# power_supply.net
KiCad netlist of a schematic drawn in Altium Designer
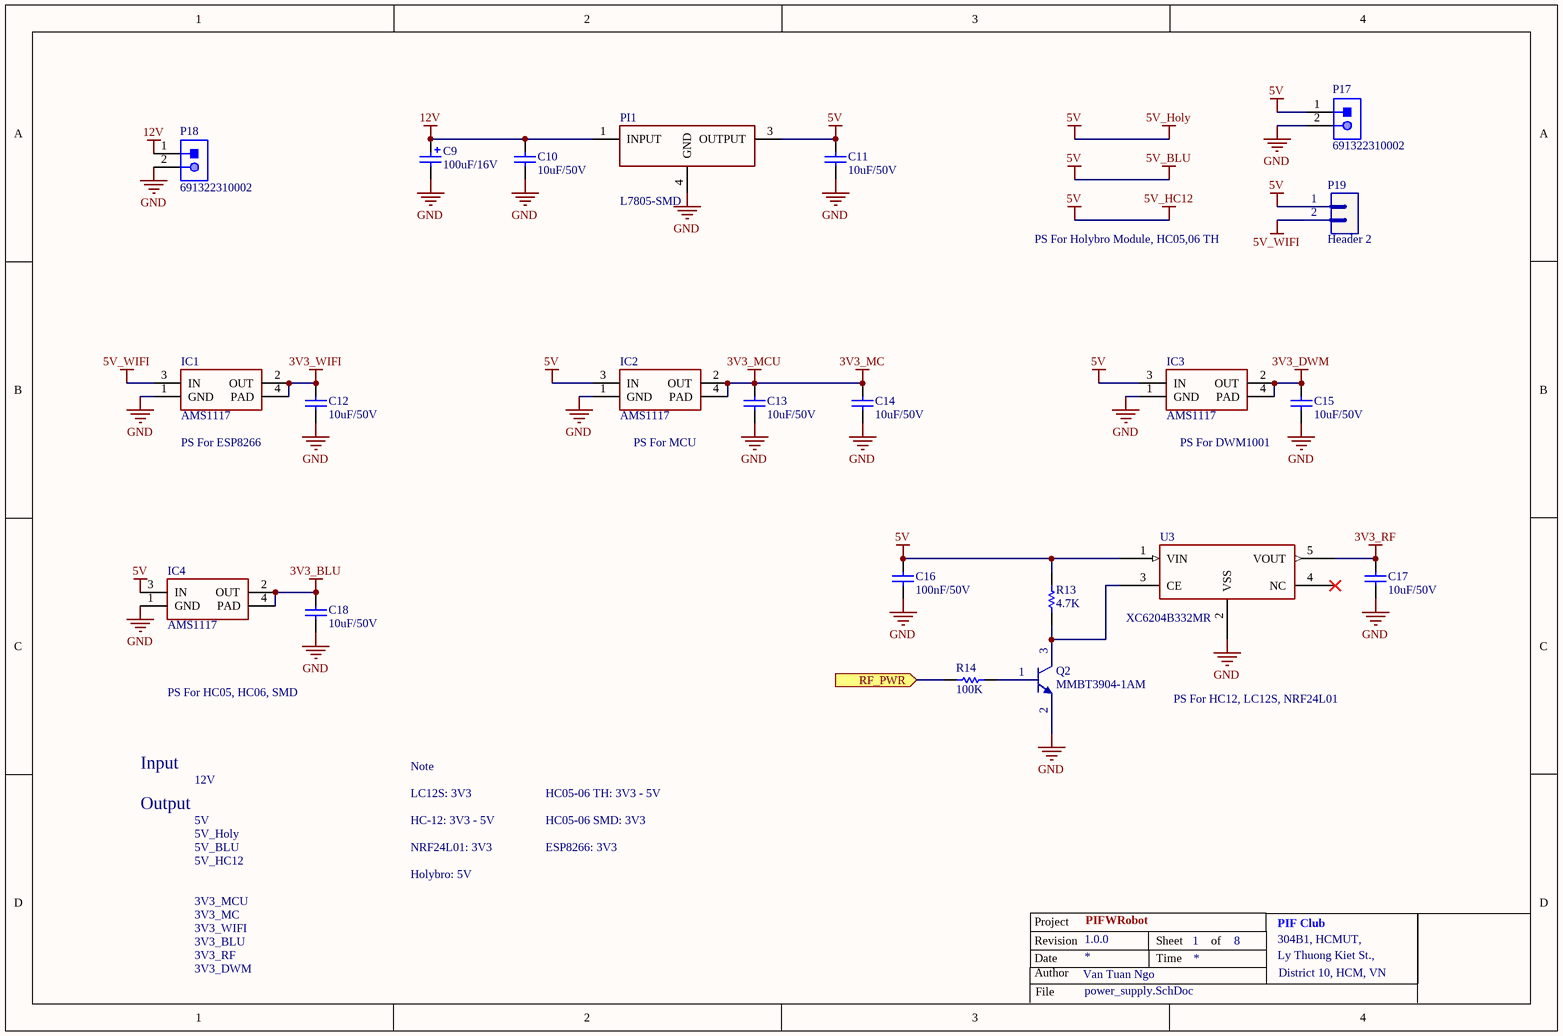
[diagram p0: power_supply.SchDoc]

(export (version "E")
  (design (tool "Eeschema 10.0.6"))
  (components
    (comp (ref "C9")
      (value "100uF/16V")
      (footprint "CAP-SM-AL-SIZE-D-D6L6")
      (description "CAP ALUM 100UF 20% 16V SMD")
      (fields
        (field (name "MANUFACTURER") "Nichicon")
        (field (name "MANUFACTURER PART NUMBER") "UWX1C101MCL1GB")
      )
      (libsource (lib "Capacitor") (part "Cap-Al-100uF-16V-D6L5"))
    )
    (comp (ref "C10")
      (value "10uF/50V")
      (footprint "CAP-SM-0805")
      (description "CAP CER 10UF 50V X5R 0805")
      (fields
        (field (name "MANUFACTURER") "Yageo")
        (field (name "MANUFACTURER PART NUMBER") "CC0805KKX5R9BB106")
      )
      (libsource (lib "Capacitor") (part "Cap-10uF-50V-0805"))
    )
    (comp (ref "C11")
      (value "10uF/50V")
      (footprint "CAP-SM-0805")
      (description "CAP CER 10UF 50V X5R 0805")
      (fields
        (field (name "MANUFACTURER") "Yageo")
        (field (name "MANUFACTURER PART NUMBER") "CC0805KKX5R9BB106")
      )
      (libsource (lib "Capacitor") (part "Cap-10uF-50V-0805"))
    )
    (comp (ref "C12")
      (value "10uF/50V")
      (footprint "CAP-SM-0805")
      (description "CAP CER 10UF 50V X5R 0805")
      (fields
        (field (name "MANUFACTURER") "Yageo")
        (field (name "MANUFACTURER PART NUMBER") "CC0805KKX5R9BB106")
      )
      (libsource (lib "Capacitor") (part "Cap-10uF-50V-0805"))
    )
    (comp (ref "C13")
      (value "10uF/50V")
      (footprint "CAP-SM-0805")
      (description "CAP CER 10UF 50V X5R 0805")
      (fields
        (field (name "MANUFACTURER") "Yageo")
        (field (name "MANUFACTURER PART NUMBER") "CC0805KKX5R9BB106")
      )
      (libsource (lib "Capacitor") (part "Cap-10uF-50V-0805"))
    )
    (comp (ref "C14")
      (value "10uF/50V")
      (footprint "CAP-SM-0805")
      (description "CAP CER 10UF 50V X5R 0805")
      (fields
        (field (name "MANUFACTURER") "Yageo")
        (field (name "MANUFACTURER PART NUMBER") "CC0805KKX5R9BB106")
      )
      (libsource (lib "Capacitor") (part "Cap-10uF-50V-0805"))
    )
    (comp (ref "C15")
      (value "10uF/50V")
      (footprint "CAP-SM-0805")
      (description "CAP CER 10UF 50V X5R 0805")
      (fields
        (field (name "MANUFACTURER") "Yageo")
        (field (name "MANUFACTURER PART NUMBER") "CC0805KKX5R9BB106")
      )
      (libsource (lib "Capacitor") (part "Cap-10uF-50V-0805"))
    )
    (comp (ref "C16")
      (value "100nF/50V")
      (footprint "CAP-SM-0805")
      (description "CAP CER 0.1UF 50V Y5V 0805")
      (fields
        (field (name "MANUFACTURER") "Samsung Electro-Mechanics")
        (field (name "MANUFACTURER PART NUMBER") "CL21F104ZBCNNNC")
      )
      (libsource (lib "Capacitor") (part "Cap-100nF-50V-0805"))
    )
    (comp (ref "C17")
      (value "10uF/50V")
      (footprint "CAP-SM-0805")
      (description "CAP CER 10UF 50V X5R 0805")
      (fields
        (field (name "MANUFACTURER") "Yageo")
        (field (name "MANUFACTURER PART NUMBER") "CC0805KKX5R9BB106")
      )
      (libsource (lib "Capacitor") (part "Cap-10uF-50V-0805"))
    )
    (comp (ref "C18")
      (value "10uF/50V")
      (footprint "CAP-SM-0805")
      (description "CAP CER 10UF 50V X5R 0805")
      (fields
        (field (name "MANUFACTURER") "Yageo")
        (field (name "MANUFACTURER PART NUMBER") "CC0805KKX5R9BB106")
      )
      (libsource (lib "Capacitor") (part "Cap-10uF-50V-0805"))
    )
    (comp (ref "IC1")
      (value "AMS1117")
      (footprint "SOT223")
      (description "Available in 1.8V, 2.5V, 2.85V, 3.3V, 5V, and  Adjustable Versions")
      (libsource (lib "PI") (part "AMS1117"))
    )
    (comp (ref "IC2")
      (value "AMS1117")
      (footprint "SOT223")
      (description "Available in 1.8V, 2.5V, 2.85V, 3.3V, 5V, and  Adjustable Versions")
      (libsource (lib "PI") (part "AMS1117"))
    )
    (comp (ref "IC3")
      (value "AMS1117")
      (footprint "SOT223")
      (description "Available in 1.8V, 2.5V, 2.85V, 3.3V, 5V, and  Adjustable Versions")
      (libsource (lib "PI") (part "AMS1117"))
    )
    (comp (ref "IC4")
      (value "AMS1117")
      (footprint "SOT223")
      (description "Available in 1.8V, 2.5V, 2.85V, 3.3V, 5V, and  Adjustable Versions")
      (libsource (lib "PI") (part "AMS1117"))
    )
    (comp (ref "P17")
      (value "691322310002")
      (footprint "691322310002")
      (description "WR-TBL Serie 322 Horizontal PCB Header, Pluggable, pitch 3.81mm, 2p")
      (fields (field (name "LOCAL SUPPLEIR PART NUMBER") "x") (field (name "PUBLISHER") "Wurth Elektronik"))
      (libsource (lib "terminal_block") (part "691322310002"))
    )
    (comp (ref "P18")
      (value "691322310002")
      (footprint "691322310002")
      (description "WR-TBL Serie 322 Horizontal PCB Header, Pluggable, pitch 3.81mm, 2p")
      (fields (field (name "LOCAL SUPPLEIR PART NUMBER") "x") (field (name "PUBLISHER") "Wurth Elektronik"))
      (libsource (lib "terminal_block") (part "691322310002"))
    )
    (comp (ref "P19")
      (value "Header 2")
      (footprint "JP2")
      (description "Header, 2-Pin")
      (fields (field (name "PUBLISHER") "Altium Limited"))
      (libsource (lib "Header-Connector") (part "Header 2"))
    )
    (comp (ref "PI1")
      (value "L7805-SMD")
      (footprint "TO254P1435X464-4N")
      (libsource (lib "PIFWRobot") (part "L7805-SMD"))
    )
    (comp (ref "Q2")
      (value "MMBT3904-1AM")
      (footprint "SOT23_NEX")
      (libsource (lib "BJT") (part "MMBT3904-1AM"))
    )
    (comp (ref "R13")
      (value "4.7K")
      (footprint "Resistor:RES-SM-0805")
      (description "RES SMD 4.7K OHM 5% 1/8W 0805")
      (fields
        (field (name "MANUFACTURER") "Yageo")
        (field (name "MANUFACTURER PART NUMBER") "RC0805JR-074K7L")
      )
      (libsource (lib "Resistor") (part "Res-4.7K-0805"))
    )
    (comp (ref "R14")
      (value "100K")
      (footprint "Resistor:RES-SM-0805")
      (description "RES 0 OHM JUMPER 0805")
      (fields
        (field (name "MANUFACTURER") "Vishay Dale")
        (field (name "MANUFACTURER PART NUMBER") "WSL080500000ZEA9")
      )
      (libsource (lib "Resistor") (part "Res-100K-0805"))
    )
    (comp (ref "U3")
      (value "XC6204B332MR")
      (footprint "XC6204/05_SOT-00")
      (fields (field (name "COPYRIGHT") "Copyright (C) 2018 Accelerated Designs. All rights reserved"))
      (libsource (lib "PI") (part "XC6204B332MR"))
    )
  )
  (nets
    (net (code "1") (name "/RF_PWR") (class "Default")
      (node (ref "R14") (pin "1") (pinfunction "1_1") (pintype "passive"))
    )
    (net (code "2") (name "3V3_BLU") (class "Default")
      (node (ref "C18") (pin "2") (pinfunction "2_2") (pintype "passive"))
      (node (ref "IC4") (pin "2") (pinfunction "OUT_2") (pintype "passive"))
      (node (ref "IC4") (pin "4") (pinfunction "PAD_4") (pintype "passive"))
    )
    (net (code "3") (name "3V3_DWM") (class "Default")
      (node (ref "C15") (pin "2") (pinfunction "2_2") (pintype "passive"))
      (node (ref "IC3") (pin "2") (pinfunction "OUT_2") (pintype "passive"))
      (node (ref "IC3") (pin "4") (pinfunction "PAD_4") (pintype "passive"))
    )
    (net (code "4") (name "3V3_MC") (class "Default")
      (node (ref "C13") (pin "2") (pinfunction "2_2") (pintype "passive"))
      (node (ref "C14") (pin "2") (pinfunction "2_2") (pintype "passive"))
      (node (ref "IC2") (pin "2") (pinfunction "OUT_2") (pintype "passive"))
      (node (ref "IC2") (pin "4") (pinfunction "PAD_4") (pintype "passive"))
    )
    (net (code "5") (name "3V3_RF") (class "Default")
      (node (ref "C17") (pin "2") (pinfunction "2_2") (pintype "passive"))
      (node (ref "U3") (pin "5") (pinfunction "VOUT_5") (pintype "output"))
    )
    (net (code "6") (name "3V3_WIFI") (class "Default")
      (node (ref "C12") (pin "2") (pinfunction "2_2") (pintype "passive"))
      (node (ref "IC1") (pin "2") (pinfunction "OUT_2") (pintype "passive"))
      (node (ref "IC1") (pin "4") (pinfunction "PAD_4") (pintype "passive"))
    )
    (net (code "7") (name "5V") (class "Default")
      (node (ref "C11") (pin "2") (pinfunction "2_2") (pintype "passive"))
      (node (ref "C16") (pin "2") (pinfunction "2_2") (pintype "passive"))
      (node (ref "IC2") (pin "3") (pinfunction "IN_3") (pintype "passive"))
      (node (ref "IC3") (pin "3") (pinfunction "IN_3") (pintype "passive"))
      (node (ref "IC4") (pin "3") (pinfunction "IN_3") (pintype "passive"))
      (node (ref "P17") (pin "1") (pinfunction "1_1") (pintype "passive"))
      (node (ref "P19") (pin "1") (pinfunction "1_1") (pintype "passive"))
      (node (ref "PI1") (pin "3") (pinfunction "OUTPUT_3") (pintype "passive"))
      (node (ref "R13") (pin "2") (pinfunction "2_2") (pintype "passive"))
      (node (ref "U3") (pin "1") (pinfunction "VIN_1") (pintype "input"))
    )
    (net (code "8") (name "5V_WIFI") (class "Default")
      (node (ref "IC1") (pin "3") (pinfunction "IN_3") (pintype "passive"))
      (node (ref "P19") (pin "2") (pinfunction "2_2") (pintype "passive"))
    )
    (net (code "9") (name "12V") (class "Default")
      (node (ref "C10") (pin "2") (pinfunction "2_2") (pintype "passive"))
      (node (ref "C9") (pin "1") (pinfunction "1_1") (pintype "passive"))
      (node (ref "P18") (pin "1") (pinfunction "1_1") (pintype "passive"))
      (node (ref "PI1") (pin "1") (pinfunction "INPUT_1") (pintype "passive"))
    )
    (net (code "10") (name "GND") (class "Default")
      (node (ref "C10") (pin "1") (pinfunction "1_1") (pintype "passive"))
      (node (ref "C11") (pin "1") (pinfunction "1_1") (pintype "passive"))
      (node (ref "C12") (pin "1") (pinfunction "1_1") (pintype "passive"))
      (node (ref "C13") (pin "1") (pinfunction "1_1") (pintype "passive"))
      (node (ref "C14") (pin "1") (pinfunction "1_1") (pintype "passive"))
      (node (ref "C15") (pin "1") (pinfunction "1_1") (pintype "passive"))
      (node (ref "C16") (pin "1") (pinfunction "1_1") (pintype "passive"))
      (node (ref "C17") (pin "1") (pinfunction "1_1") (pintype "passive"))
      (node (ref "C18") (pin "1") (pinfunction "1_1") (pintype "passive"))
      (node (ref "C9") (pin "2") (pinfunction "2_2") (pintype "passive"))
      (node (ref "IC1") (pin "1") (pinfunction "GND_1") (pintype "passive"))
      (node (ref "IC2") (pin "1") (pinfunction "GND_1") (pintype "passive"))
      (node (ref "IC3") (pin "1") (pinfunction "GND_1") (pintype "passive"))
      (node (ref "IC4") (pin "1") (pinfunction "GND_1") (pintype "passive"))
      (node (ref "P17") (pin "2") (pinfunction "2_2") (pintype "passive"))
      (node (ref "P18") (pin "2") (pinfunction "2_2") (pintype "passive"))
      (node (ref "PI1") (pin "4") (pinfunction "GND_4") (pintype "passive"))
      (node (ref "Q2") (pin "2") (pinfunction "E_2") (pintype "passive"))
      (node (ref "U3") (pin "2") (pinfunction "VSS_2") (pintype "passive"))
    )
    (net (code "11") (name "Net-(Q2-B)") (class "Default")
      (node (ref "Q2") (pin "1") (pinfunction "B_1") (pintype "passive"))
      (node (ref "R14") (pin "2") (pinfunction "2_2") (pintype "passive"))
    )
    (net (code "12") (name "Net-(Q2-C)") (class "Default")
      (node (ref "Q2") (pin "3") (pinfunction "C_3") (pintype "passive"))
      (node (ref "R13") (pin "1") (pinfunction "1_1") (pintype "passive"))
      (node (ref "U3") (pin "3") (pinfunction "CE_3") (pintype "passive"))
    )
    (net (code "13") (name "unconnected-(U3-NC-Pad4)") (class "Default")
      (node (ref "U3") (pin "4") (pinfunction "NC_4") (pintype "passive+no_connect"))
    )
  )
)
